# Bipolary.net
KiCad netlist of a schematic drawn in EAGLE
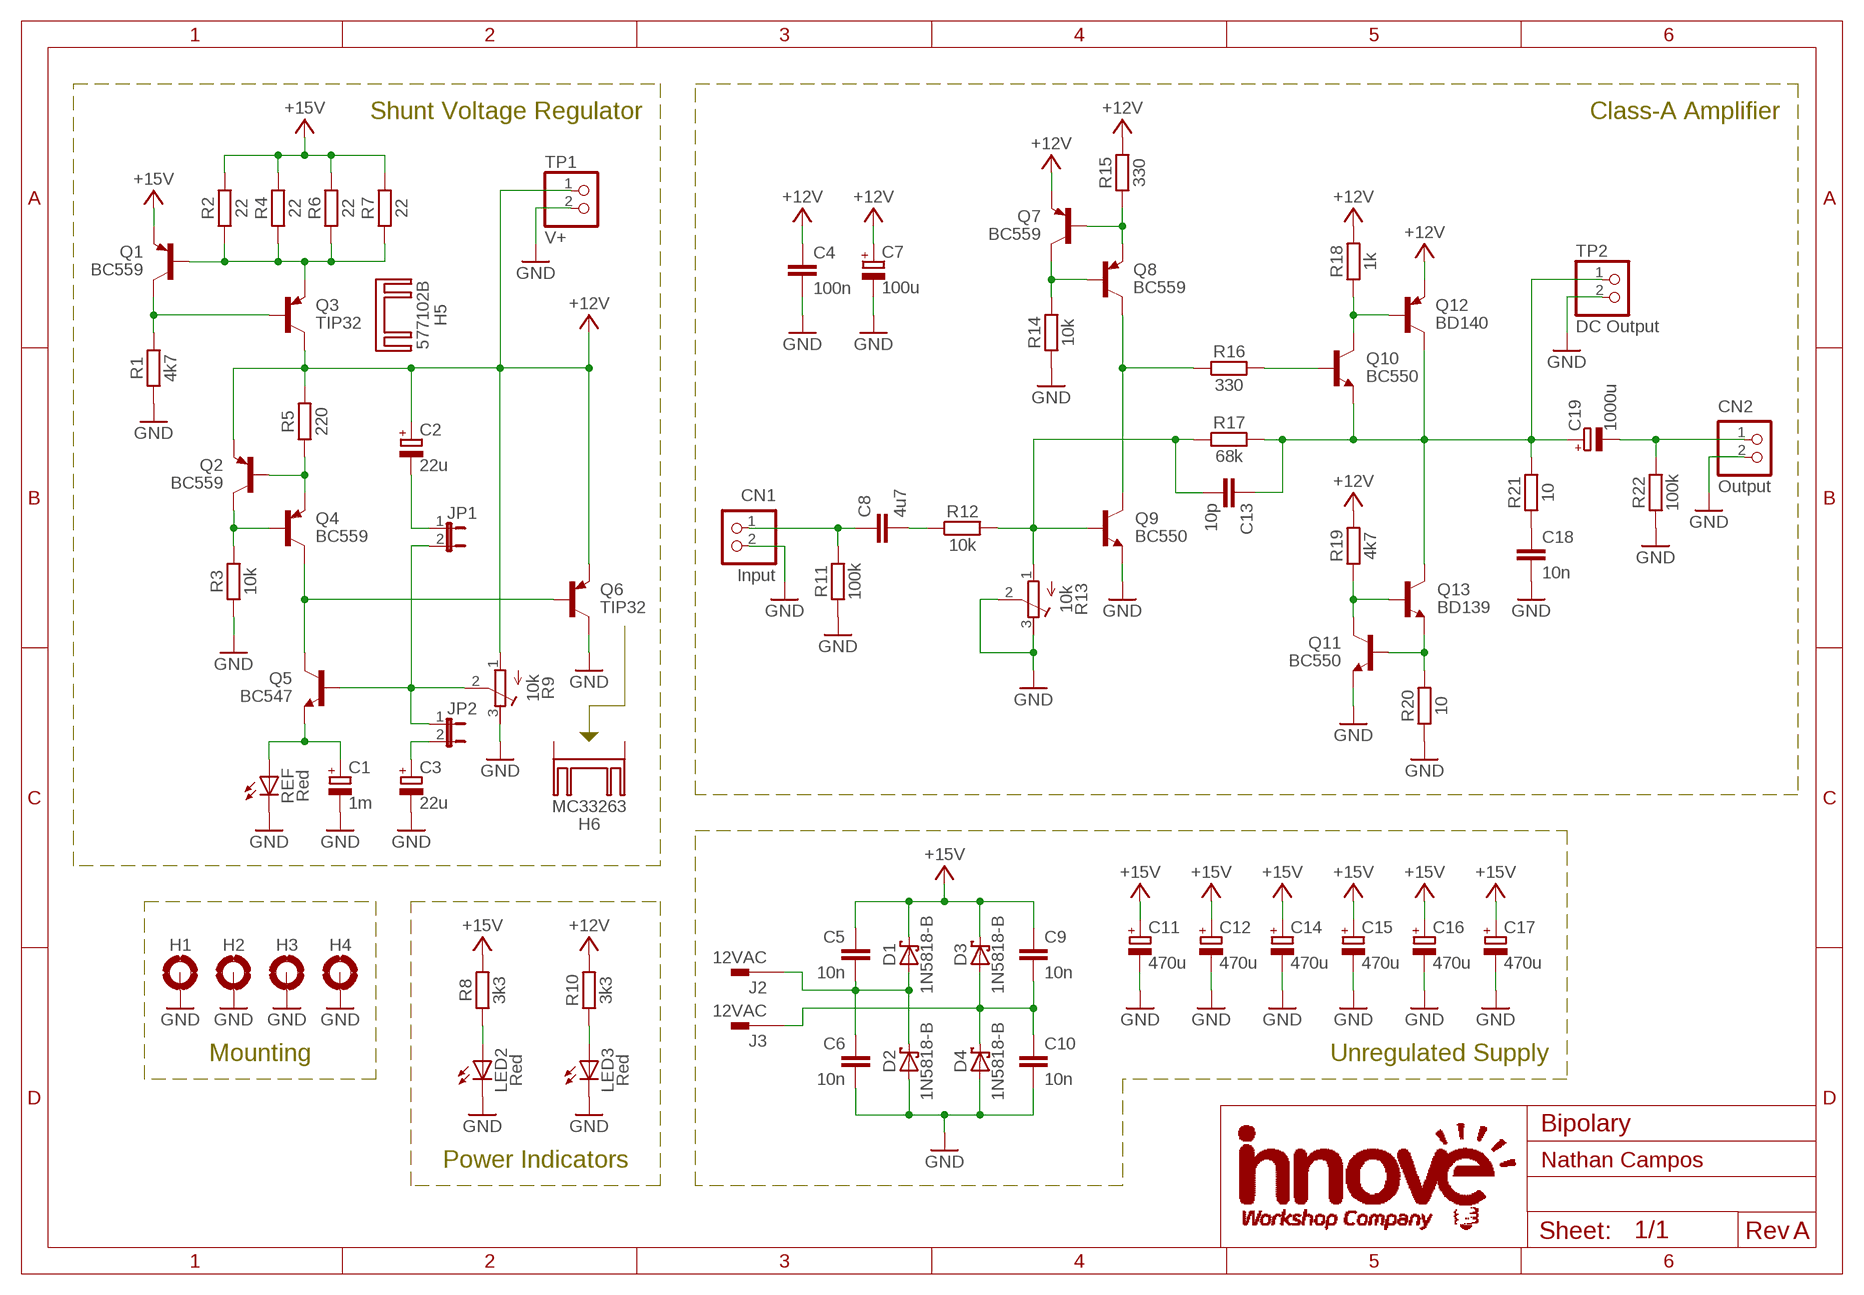
[diagram p0: schematic, sheet 1]

(export (version "E")
  (design (tool "Eeschema 10.0.6"))
  (components
    (comp (ref "C1")
      (value "1m")
      (footprint "eagle-import:E3,5-8")
      (libsource (lib "eagle-import") (part "CPOL-E3.5-8"))
    )
    (comp (ref "C2")
      (value "22u")
      (footprint "eagle-import:E2-5")
      (libsource (lib "eagle-import") (part "CPOL-E2-5"))
    )
    (comp (ref "C3")
      (value "22u")
      (footprint "eagle-import:E2-5")
      (libsource (lib "eagle-import") (part "CPOL-E2-5"))
    )
    (comp (ref "C4")
      (value "100n")
      (footprint "eagle-import:C050-025X075")
      (libsource (lib "eagle-import") (part "C5.0-2.5X7.5"))
    )
    (comp (ref "C5")
      (value "10n")
      (footprint "eagle-import:C050-025X075")
      (libsource (lib "eagle-import") (part "C5.0-2.5X7.5"))
    )
    (comp (ref "C6")
      (value "10n")
      (footprint "eagle-import:C050-025X075")
      (libsource (lib "eagle-import") (part "C5.0-2.5X7.5"))
    )
    (comp (ref "C7")
      (value "100u")
      (footprint "eagle-import:E3,5-8")
      (libsource (lib "eagle-import") (part "CPOL-E3.5-8"))
    )
    (comp (ref "C8")
      (value "4u7")
      (footprint "eagle-import:C150-084X183")
      (libsource (lib "eagle-import") (part "C15-8.4X18.3"))
    )
    (comp (ref "C9")
      (value "10n")
      (footprint "eagle-import:C050-025X075")
      (libsource (lib "eagle-import") (part "C5.0-2.5X7.5"))
    )
    (comp (ref "C10")
      (value "10n")
      (footprint "eagle-import:C050-025X075")
      (libsource (lib "eagle-import") (part "C5.0-2.5X7.5"))
    )
    (comp (ref "C11")
      (value "470u")
      (footprint "eagle-import:E5-10")
      (libsource (lib "eagle-import") (part "CPOL-E5-10"))
    )
    (comp (ref "C12")
      (value "470u")
      (footprint "eagle-import:E5-10")
      (libsource (lib "eagle-import") (part "CPOL-E5-10"))
    )
    (comp (ref "C13")
      (value "10p")
      (footprint "eagle-import:C050-025X075")
      (libsource (lib "eagle-import") (part "C5.0-2.5X7.5"))
    )
    (comp (ref "C14")
      (value "470u")
      (footprint "eagle-import:E5-10")
      (libsource (lib "eagle-import") (part "CPOL-E5-10"))
    )
    (comp (ref "C15")
      (value "470u")
      (footprint "eagle-import:E5-10")
      (libsource (lib "eagle-import") (part "CPOL-E5-10"))
    )
    (comp (ref "C16")
      (value "470u")
      (footprint "eagle-import:E5-10")
      (libsource (lib "eagle-import") (part "CPOL-E5-10"))
    )
    (comp (ref "C17")
      (value "470u")
      (footprint "eagle-import:E5-10")
      (libsource (lib "eagle-import") (part "CPOL-E5-10"))
    )
    (comp (ref "C18")
      (value "10n")
      (footprint "eagle-import:C050-025X075")
      (libsource (lib "eagle-import") (part "C5.0-2.5X7.5"))
    )
    (comp (ref "C19")
      (value "1000u")
      (footprint "eagle-import:E5-10")
      (libsource (lib "eagle-import") (part "CPOL-E5-10"))
    )
    (comp (ref "CN1")
      (value "Input")
      (footprint "eagle-import:B2B-XH-A")
      (libsource (lib "eagle-import") (part "B2B-XH-A"))
    )
    (comp (ref "CN2")
      (value "Output")
      (footprint "eagle-import:B2B-XH-A")
      (libsource (lib "eagle-import") (part "B2B-XH-A"))
    )
    (comp (ref "D1")
      (value "1N5818-B")
      (footprint "eagle-import:DO41-7.6")
      (libsource (lib "eagle-import") (part "1N5818-B"))
    )
    (comp (ref "D2")
      (value "1N5818-B")
      (footprint "eagle-import:DO41-7.6")
      (libsource (lib "eagle-import") (part "1N5818-B"))
    )
    (comp (ref "D3")
      (value "1N5818-B")
      (footprint "eagle-import:DO41-7.6")
      (libsource (lib "eagle-import") (part "1N5818-B"))
    )
    (comp (ref "D4")
      (value "1N5818-B")
      (footprint "eagle-import:DO41-7.6")
      (libsource (lib "eagle-import") (part "1N5818-B"))
    )
    (comp (ref "H1")
      (value "MOUNT-PAD-ROUND3.0")
      (footprint "eagle-import:3,0-PAD")
      (libsource (lib "eagle-import") (part "MOUNT-PAD-ROUND3.0"))
    )
    (comp (ref "H2")
      (value "MOUNT-PAD-ROUND3.0")
      (footprint "eagle-import:3,0-PAD")
      (libsource (lib "eagle-import") (part "MOUNT-PAD-ROUND3.0"))
    )
    (comp (ref "H3")
      (value "MOUNT-PAD-ROUND3.0")
      (footprint "eagle-import:3,0-PAD")
      (libsource (lib "eagle-import") (part "MOUNT-PAD-ROUND3.0"))
    )
    (comp (ref "H4")
      (value "MOUNT-PAD-ROUND3.0")
      (footprint "eagle-import:3,0-PAD")
      (libsource (lib "eagle-import") (part "MOUNT-PAD-ROUND3.0"))
    )
    (comp (ref "H5")
      (value "577102B")
      (footprint "eagle-import:D02S")
      (libsource (lib "eagle-import") (part "577102B"))
    )
    (comp (ref "H6")
      (value "MC33263")
      (footprint "eagle-import:SK104-PAD")
      (libsource (lib "eagle-import") (part "MC33263"))
    )
    (comp (ref "J2")
      (value "12VAC")
      (footprint "eagle-import:F061.100")
      (libsource (lib "eagle-import") (part "FASTON-250D140"))
    )
    (comp (ref "J3")
      (value "12VAC")
      (footprint "eagle-import:F061.100")
      (libsource (lib "eagle-import") (part "FASTON-250D140"))
    )
    (comp (ref "JP1")
      (value "JP1E")
      (footprint "eagle-import:JP1")
      (libsource (lib "eagle-import") (part "JP1E"))
    )
    (comp (ref "JP2")
      (value "JP1E")
      (footprint "eagle-import:JP1")
      (libsource (lib "eagle-import") (part "JP1E"))
    )
    (comp (ref "LED2")
      (value "Red")
      (footprint "eagle-import:LED5MM")
      (libsource (lib "eagle-import") (part "LED5MM"))
    )
    (comp (ref "LED3")
      (value "Red")
      (footprint "eagle-import:LED5MM")
      (libsource (lib "eagle-import") (part "LED5MM"))
    )
    (comp (ref "Q1")
      (value "BC559")
      (footprint "eagle-import:TO92")
      (libsource (lib "eagle-import") (part "BC559"))
    )
    (comp (ref "Q2")
      (value "BC559")
      (footprint "eagle-import:TO92")
      (libsource (lib "eagle-import") (part "BC559"))
    )
    (comp (ref "Q3")
      (value "TIP32")
      (footprint "eagle-import:TO220V")
      (libsource (lib "eagle-import") (part "TIP32"))
    )
    (comp (ref "Q4")
      (value "BC559")
      (footprint "eagle-import:TO92")
      (libsource (lib "eagle-import") (part "BC559"))
    )
    (comp (ref "Q5")
      (value "BC547")
      (footprint "eagle-import:TO92")
      (libsource (lib "eagle-import") (part "BC547"))
    )
    (comp (ref "Q6")
      (value "TIP32")
      (footprint "eagle-import:TO220V")
      (libsource (lib "eagle-import") (part "TIP32"))
    )
    (comp (ref "Q7")
      (value "BC559")
      (footprint "eagle-import:TO92")
      (libsource (lib "eagle-import") (part "BC559"))
    )
    (comp (ref "Q8")
      (value "BC559")
      (footprint "eagle-import:TO92")
      (libsource (lib "eagle-import") (part "BC559"))
    )
    (comp (ref "Q9")
      (value "BC550")
      (footprint "eagle-import:TO92")
      (libsource (lib "eagle-import") (part "BC550"))
    )
    (comp (ref "Q10")
      (value "BC550")
      (footprint "eagle-import:TO92")
      (libsource (lib "eagle-import") (part "BC550"))
    )
    (comp (ref "Q11")
      (value "BC550")
      (footprint "eagle-import:TO92")
      (libsource (lib "eagle-import") (part "BC550"))
    )
    (comp (ref "Q12")
      (value "BD140")
      (footprint "eagle-import:TO126V")
      (libsource (lib "eagle-import") (part "BD140"))
    )
    (comp (ref "Q13")
      (value "BD139")
      (footprint "eagle-import:TO126V")
      (libsource (lib "eagle-import") (part "BD139"))
    )
    (comp (ref "R1")
      (value "4k7")
      (footprint "eagle-import:0207_10")
      (libsource (lib "eagle-import") (part "RT0207"))
    )
    (comp (ref "R2")
      (value "22")
      (footprint "eagle-import:0207_10")
      (libsource (lib "eagle-import") (part "RT0207"))
    )
    (comp (ref "R3")
      (value "10k")
      (footprint "eagle-import:0207_10")
      (libsource (lib "eagle-import") (part "RT0207"))
    )
    (comp (ref "R4")
      (value "22")
      (footprint "eagle-import:0207_10")
      (libsource (lib "eagle-import") (part "RT0207"))
    )
    (comp (ref "R5")
      (value "220")
      (footprint "eagle-import:0207_10")
      (libsource (lib "eagle-import") (part "RT0207"))
    )
    (comp (ref "R6")
      (value "22")
      (footprint "eagle-import:0207_10")
      (libsource (lib "eagle-import") (part "RT0207"))
    )
    (comp (ref "R7")
      (value "22")
      (footprint "eagle-import:0207_10")
      (libsource (lib "eagle-import") (part "RT0207"))
    )
    (comp (ref "R8")
      (value "3k3")
      (footprint "eagle-import:0207_10")
      (libsource (lib "eagle-import") (part "RT0207"))
    )
    (comp (ref "R9")
      (value "10k")
      (footprint "eagle-import:RTRIM3296Y")
      (libsource (lib "eagle-import") (part "R-TRIMM3296Y"))
    )
    (comp (ref "R10")
      (value "3k3")
      (footprint "eagle-import:0207_10")
      (libsource (lib "eagle-import") (part "RT0207"))
    )
    (comp (ref "R11")
      (value "100k")
      (footprint "eagle-import:0207_10")
      (libsource (lib "eagle-import") (part "RT0207"))
    )
    (comp (ref "R12")
      (value "10k")
      (footprint "eagle-import:0207_10")
      (libsource (lib "eagle-import") (part "RT0207"))
    )
    (comp (ref "R13")
      (value "10k")
      (footprint "eagle-import:RTRIM3296Y")
      (libsource (lib "eagle-import") (part "R-TRIMM3296Y"))
    )
    (comp (ref "R14")
      (value "10k")
      (footprint "eagle-import:0207_10")
      (libsource (lib "eagle-import") (part "RT0207"))
    )
    (comp (ref "R15")
      (value "330")
      (footprint "eagle-import:0207_10")
      (libsource (lib "eagle-import") (part "RT0207"))
    )
    (comp (ref "R16")
      (value "330")
      (footprint "eagle-import:0207_10")
      (libsource (lib "eagle-import") (part "RT0207"))
    )
    (comp (ref "R17")
      (value "68k")
      (footprint "eagle-import:0207_10")
      (libsource (lib "eagle-import") (part "RT0207"))
    )
    (comp (ref "R18")
      (value "1k")
      (footprint "eagle-import:0207_10")
      (libsource (lib "eagle-import") (part "RT0207"))
    )
    (comp (ref "R19")
      (value "4k7")
      (footprint "eagle-import:0207_10")
      (libsource (lib "eagle-import") (part "RT0207"))
    )
    (comp (ref "R20")
      (value "10")
      (footprint "eagle-import:0207_10")
      (libsource (lib "eagle-import") (part "RT0207"))
    )
    (comp (ref "R21")
      (value "10")
      (footprint "eagle-import:0207_10")
      (libsource (lib "eagle-import") (part "RT0207"))
    )
    (comp (ref "R22")
      (value "100k")
      (footprint "eagle-import:0207_10")
      (libsource (lib "eagle-import") (part "RT0207"))
    )
    (comp (ref "REF")
      (value "Red")
      (footprint "eagle-import:LED5MM")
      (libsource (lib "eagle-import") (part "LED5MM"))
    )
    (comp (ref "TP1")
      (value "V+")
      (footprint "eagle-import:1X02")
      (libsource (lib "eagle-import") (part "PINHD-1X2"))
    )
    (comp (ref "TP2")
      (value "DC Output")
      (footprint "eagle-import:1X02")
      (libsource (lib "eagle-import") (part "PINHD-1X2"))
    )
  )
  (nets
    (net (code "1") (name "+12V") (class "Default")
      (node (ref "C2") (pin "+") (pinfunction "+_+") (pintype "passive"))
      (node (ref "C4") (pin "1") (pinfunction "1_1") (pintype "passive"))
      (node (ref "C7") (pin "+") (pinfunction "+_+") (pintype "passive"))
      (node (ref "Q12") (pin "1") (pinfunction "E_1") (pintype "passive"))
      (node (ref "Q2") (pin "3") (pinfunction "E_3") (pintype "passive"))
      (node (ref "Q3") (pin "2") (pinfunction "C_2") (pintype "passive"))
      (node (ref "Q6") (pin "3") (pinfunction "E_3") (pintype "passive"))
      (node (ref "Q7") (pin "3") (pinfunction "E_3") (pintype "passive"))
      (node (ref "R10") (pin "2") (pinfunction "2_2") (pintype "passive"))
      (node (ref "R15") (pin "2") (pinfunction "2_2") (pintype "passive"))
      (node (ref "R18") (pin "2") (pinfunction "2_2") (pintype "passive"))
      (node (ref "R19") (pin "2") (pinfunction "2_2") (pintype "passive"))
      (node (ref "R5") (pin "2") (pinfunction "2_2") (pintype "passive"))
      (node (ref "R9") (pin "1") (pinfunction "A_1") (pintype "passive"))
      (node (ref "TP1") (pin "1") (pinfunction "1_1") (pintype "passive"))
    )
    (net (code "2") (name "+15V") (class "Default")
      (node (ref "C11") (pin "+") (pinfunction "+_+") (pintype "passive"))
      (node (ref "C12") (pin "+") (pinfunction "+_+") (pintype "passive"))
      (node (ref "C14") (pin "+") (pinfunction "+_+") (pintype "passive"))
      (node (ref "C15") (pin "+") (pinfunction "+_+") (pintype "passive"))
      (node (ref "C16") (pin "+") (pinfunction "+_+") (pintype "passive"))
      (node (ref "C17") (pin "+") (pinfunction "+_+") (pintype "passive"))
      (node (ref "C5") (pin "1") (pinfunction "1_1") (pintype "passive"))
      (node (ref "C9") (pin "1") (pinfunction "1_1") (pintype "passive"))
      (node (ref "D1") (pin "C") (pinfunction "C_C") (pintype "passive"))
      (node (ref "D3") (pin "C") (pinfunction "C_C") (pintype "passive"))
      (node (ref "Q1") (pin "3") (pinfunction "E_3") (pintype "passive"))
      (node (ref "R2") (pin "2") (pinfunction "2_2") (pintype "passive"))
      (node (ref "R4") (pin "2") (pinfunction "2_2") (pintype "passive"))
      (node (ref "R6") (pin "2") (pinfunction "2_2") (pintype "passive"))
      (node (ref "R7") (pin "2") (pinfunction "2_2") (pintype "passive"))
      (node (ref "R8") (pin "2") (pinfunction "2_2") (pintype "passive"))
    )
    (net (code "3") (name "GND") (class "Default")
      (node (ref "C1") (pin "-") (pinfunction "-_-") (pintype "passive"))
      (node (ref "C10") (pin "2") (pinfunction "2_2") (pintype "passive"))
      (node (ref "C11") (pin "-") (pinfunction "-_-") (pintype "passive"))
      (node (ref "C12") (pin "-") (pinfunction "-_-") (pintype "passive"))
      (node (ref "C14") (pin "-") (pinfunction "-_-") (pintype "passive"))
      (node (ref "C15") (pin "-") (pinfunction "-_-") (pintype "passive"))
      (node (ref "C16") (pin "-") (pinfunction "-_-") (pintype "passive"))
      (node (ref "C17") (pin "-") (pinfunction "-_-") (pintype "passive"))
      (node (ref "C18") (pin "2") (pinfunction "2_2") (pintype "passive"))
      (node (ref "C3") (pin "-") (pinfunction "-_-") (pintype "passive"))
      (node (ref "C4") (pin "2") (pinfunction "2_2") (pintype "passive"))
      (node (ref "C6") (pin "2") (pinfunction "2_2") (pintype "passive"))
      (node (ref "C7") (pin "-") (pinfunction "-_-") (pintype "passive"))
      (node (ref "CN1") (pin "2") (pinfunction "2_2") (pintype "passive"))
      (node (ref "CN2") (pin "2") (pinfunction "2_2") (pintype "passive"))
      (node (ref "D2") (pin "A") (pinfunction "A_A") (pintype "passive"))
      (node (ref "D4") (pin "A") (pinfunction "A_A") (pintype "passive"))
      (node (ref "H1") (pin "B3,0") (pinfunction "MOUNT_B3,0") (pintype "passive"))
      (node (ref "H2") (pin "B3,0") (pinfunction "MOUNT_B3,0") (pintype "passive"))
      (node (ref "H3") (pin "B3,0") (pinfunction "MOUNT_B3,0") (pintype "passive"))
      (node (ref "H4") (pin "B3,0") (pinfunction "MOUNT_B3,0") (pintype "passive"))
      (node (ref "LED2") (pin "K") (pinfunction "C_K") (pintype "passive"))
      (node (ref "LED3") (pin "K") (pinfunction "C_K") (pintype "passive"))
      (node (ref "Q11") (pin "3") (pinfunction "E_3") (pintype "passive"))
      (node (ref "Q6") (pin "2") (pinfunction "C_2") (pintype "passive"))
      (node (ref "Q9") (pin "3") (pinfunction "E_3") (pintype "passive"))
      (node (ref "R1") (pin "1") (pinfunction "1_1") (pintype "passive"))
      (node (ref "R11") (pin "1") (pinfunction "1_1") (pintype "passive"))
      (node (ref "R13") (pin "2") (pinfunction "S_2") (pintype "passive"))
      (node (ref "R13") (pin "3") (pinfunction "E_3") (pintype "passive"))
      (node (ref "R14") (pin "1") (pinfunction "1_1") (pintype "passive"))
      (node (ref "R20") (pin "1") (pinfunction "1_1") (pintype "passive"))
      (node (ref "R22") (pin "1") (pinfunction "1_1") (pintype "passive"))
      (node (ref "R3") (pin "1") (pinfunction "1_1") (pintype "passive"))
      (node (ref "R9") (pin "3") (pinfunction "E_3") (pintype "passive"))
      (node (ref "REF") (pin "K") (pinfunction "C_K") (pintype "passive"))
      (node (ref "TP1") (pin "2") (pinfunction "2_2") (pintype "passive"))
      (node (ref "TP2") (pin "2") (pinfunction "2_2") (pintype "passive"))
    )
    (net (code "4") (name "Net-(C2-Pad-)") (class "Default")
      (node (ref "C2") (pin "-") (pinfunction "-_-") (pintype "passive"))
      (node (ref "JP1") (pin "1") (pinfunction "1_1") (pintype "passive"))
    )
    (net (code "5") (name "Net-(C3-Pad+)") (class "Default")
      (node (ref "C3") (pin "+") (pinfunction "+_+") (pintype "passive"))
      (node (ref "JP2") (pin "2") (pinfunction "2_2") (pintype "passive"))
    )
    (net (code "6") (name "Net-(C5-Pad2)") (class "Default")
      (node (ref "C5") (pin "2") (pinfunction "2_2") (pintype "passive"))
      (node (ref "C6") (pin "1") (pinfunction "1_1") (pintype "passive"))
      (node (ref "D1") (pin "A") (pinfunction "A_A") (pintype "passive"))
      (node (ref "D2") (pin "C") (pinfunction "C_C") (pintype "passive"))
      (node (ref "J2") (pin "A1") (pinfunction "1_A1") (pintype "passive"))
      (node (ref "J2") (pin "A2") (pinfunction "1_A2") (pintype "passive"))
    )
    (net (code "7") (name "Net-(C8-Pad1)") (class "Default")
      (node (ref "C8") (pin "1") (pinfunction "1_1") (pintype "passive"))
      (node (ref "CN1") (pin "1") (pinfunction "1_1") (pintype "passive"))
      (node (ref "R11") (pin "2") (pinfunction "2_2") (pintype "passive"))
    )
    (net (code "8") (name "Net-(C8-Pad2)") (class "Default")
      (node (ref "C8") (pin "2") (pinfunction "2_2") (pintype "passive"))
      (node (ref "R12") (pin "1") (pinfunction "1_1") (pintype "passive"))
    )
    (net (code "9") (name "Net-(C10-Pad1)") (class "Default")
      (node (ref "C10") (pin "1") (pinfunction "1_1") (pintype "passive"))
      (node (ref "C9") (pin "2") (pinfunction "2_2") (pintype "passive"))
      (node (ref "D3") (pin "A") (pinfunction "A_A") (pintype "passive"))
      (node (ref "D4") (pin "C") (pinfunction "C_C") (pintype "passive"))
      (node (ref "J3") (pin "A1") (pinfunction "1_A1") (pintype "passive"))
      (node (ref "J3") (pin "A2") (pinfunction "1_A2") (pintype "passive"))
    )
    (net (code "10") (name "Net-(C18-Pad1)") (class "Default")
      (node (ref "C18") (pin "1") (pinfunction "1_1") (pintype "passive"))
      (node (ref "R21") (pin "1") (pinfunction "1_1") (pintype "passive"))
    )
    (net (code "11") (name "Net-(C19-Pad-)") (class "Default")
      (node (ref "C19") (pin "-") (pinfunction "-_-") (pintype "passive"))
      (node (ref "CN2") (pin "1") (pinfunction "1_1") (pintype "passive"))
      (node (ref "R22") (pin "2") (pinfunction "2_2") (pintype "passive"))
    )
    (net (code "12") (name "Net-(LED2-PadA)") (class "Default")
      (node (ref "LED2") (pin "A") (pinfunction "A_A") (pintype "passive"))
      (node (ref "R8") (pin "1") (pinfunction "1_1") (pintype "passive"))
    )
    (net (code "13") (name "Net-(LED3-PadA)") (class "Default")
      (node (ref "LED3") (pin "A") (pinfunction "A_A") (pintype "passive"))
      (node (ref "R10") (pin "1") (pinfunction "1_1") (pintype "passive"))
    )
    (net (code "14") (name "Net-(Q1-B)") (class "Default")
      (node (ref "Q1") (pin "2") (pinfunction "B_2") (pintype "passive"))
      (node (ref "Q3") (pin "3") (pinfunction "E_3") (pintype "passive"))
      (node (ref "R2") (pin "1") (pinfunction "1_1") (pintype "passive"))
      (node (ref "R4") (pin "1") (pinfunction "1_1") (pintype "passive"))
      (node (ref "R6") (pin "1") (pinfunction "1_1") (pintype "passive"))
      (node (ref "R7") (pin "1") (pinfunction "1_1") (pintype "passive"))
    )
    (net (code "15") (name "Net-(Q1-C)") (class "Default")
      (node (ref "Q1") (pin "1") (pinfunction "C_1") (pintype "passive"))
      (node (ref "Q3") (pin "1") (pinfunction "B_1") (pintype "passive"))
      (node (ref "R1") (pin "2") (pinfunction "2_2") (pintype "passive"))
    )
    (net (code "16") (name "Net-(Q2-B)") (class "Default")
      (node (ref "Q2") (pin "2") (pinfunction "B_2") (pintype "passive"))
      (node (ref "Q4") (pin "3") (pinfunction "E_3") (pintype "passive"))
      (node (ref "R5") (pin "1") (pinfunction "1_1") (pintype "passive"))
    )
    (net (code "17") (name "Net-(Q2-C)") (class "Default")
      (node (ref "Q2") (pin "1") (pinfunction "C_1") (pintype "passive"))
      (node (ref "Q4") (pin "2") (pinfunction "B_2") (pintype "passive"))
      (node (ref "R3") (pin "2") (pinfunction "2_2") (pintype "passive"))
    )
    (net (code "18") (name "Net-(Q4-C)") (class "Default")
      (node (ref "Q4") (pin "1") (pinfunction "C_1") (pintype "passive"))
      (node (ref "Q5") (pin "1") (pinfunction "C_1") (pintype "passive"))
      (node (ref "Q6") (pin "1") (pinfunction "B_1") (pintype "passive"))
    )
    (net (code "19") (name "Net-(Q5-B)") (class "Default")
      (node (ref "JP1") (pin "2") (pinfunction "2_2") (pintype "passive"))
      (node (ref "JP2") (pin "1") (pinfunction "1_1") (pintype "passive"))
      (node (ref "Q5") (pin "2") (pinfunction "B_2") (pintype "passive"))
      (node (ref "R9") (pin "2") (pinfunction "S_2") (pintype "passive"))
    )
    (net (code "20") (name "Net-(Q5-E)") (class "Default")
      (node (ref "C1") (pin "+") (pinfunction "+_+") (pintype "passive"))
      (node (ref "Q5") (pin "3") (pinfunction "E_3") (pintype "passive"))
      (node (ref "REF") (pin "A") (pinfunction "A_A") (pintype "passive"))
    )
    (net (code "21") (name "Net-(Q7-B)") (class "Default")
      (node (ref "Q7") (pin "2") (pinfunction "B_2") (pintype "passive"))
      (node (ref "Q8") (pin "3") (pinfunction "E_3") (pintype "passive"))
      (node (ref "R15") (pin "1") (pinfunction "1_1") (pintype "passive"))
    )
    (net (code "22") (name "Net-(Q7-C)") (class "Default")
      (node (ref "Q7") (pin "1") (pinfunction "C_1") (pintype "passive"))
      (node (ref "Q8") (pin "2") (pinfunction "B_2") (pintype "passive"))
      (node (ref "R14") (pin "2") (pinfunction "2_2") (pintype "passive"))
    )
    (net (code "23") (name "Net-(Q8-C)") (class "Default")
      (node (ref "Q8") (pin "1") (pinfunction "C_1") (pintype "passive"))
      (node (ref "Q9") (pin "1") (pinfunction "C_1") (pintype "passive"))
      (node (ref "R16") (pin "1") (pinfunction "1_1") (pintype "passive"))
    )
    (net (code "24") (name "Net-(Q9-B)") (class "Default")
      (node (ref "C13") (pin "2") (pinfunction "2_2") (pintype "passive"))
      (node (ref "Q9") (pin "2") (pinfunction "B_2") (pintype "passive"))
      (node (ref "R12") (pin "2") (pinfunction "2_2") (pintype "passive"))
      (node (ref "R13") (pin "1") (pinfunction "A_1") (pintype "passive"))
      (node (ref "R17") (pin "1") (pinfunction "1_1") (pintype "passive"))
    )
    (net (code "25") (name "Net-(Q10-B)") (class "Default")
      (node (ref "Q10") (pin "2") (pinfunction "B_2") (pintype "passive"))
      (node (ref "R16") (pin "2") (pinfunction "2_2") (pintype "passive"))
    )
    (net (code "26") (name "Net-(Q10-C)") (class "Default")
      (node (ref "Q10") (pin "1") (pinfunction "C_1") (pintype "passive"))
      (node (ref "Q12") (pin "3") (pinfunction "B_3") (pintype "passive"))
      (node (ref "R18") (pin "1") (pinfunction "1_1") (pintype "passive"))
    )
    (net (code "27") (name "Net-(Q10-E)") (class "Default")
      (node (ref "C13") (pin "1") (pinfunction "1_1") (pintype "passive"))
      (node (ref "C19") (pin "+") (pinfunction "+_+") (pintype "passive"))
      (node (ref "Q10") (pin "3") (pinfunction "E_3") (pintype "passive"))
      (node (ref "Q12") (pin "2") (pinfunction "C_2") (pintype "passive"))
      (node (ref "Q13") (pin "2") (pinfunction "C_2") (pintype "passive"))
      (node (ref "R17") (pin "2") (pinfunction "2_2") (pintype "passive"))
      (node (ref "R21") (pin "2") (pinfunction "2_2") (pintype "passive"))
      (node (ref "TP2") (pin "1") (pinfunction "1_1") (pintype "passive"))
    )
    (net (code "28") (name "Net-(Q11-B)") (class "Default")
      (node (ref "Q11") (pin "2") (pinfunction "B_2") (pintype "passive"))
      (node (ref "Q13") (pin "1") (pinfunction "E_1") (pintype "passive"))
      (node (ref "R20") (pin "2") (pinfunction "2_2") (pintype "passive"))
    )
    (net (code "29") (name "Net-(Q11-C)") (class "Default")
      (node (ref "Q11") (pin "1") (pinfunction "C_1") (pintype "passive"))
      (node (ref "Q13") (pin "3") (pinfunction "B_3") (pintype "passive"))
      (node (ref "R19") (pin "1") (pinfunction "1_1") (pintype "passive"))
    )
    (net (code "30") (name "unconnected-(H6-K-PadK1)") (class "Default")
      (node (ref "H6") (pin "K1") (pinfunction "K_K1") (pintype "passive"))
    )
    (net (code "31") (name "unconnected-(H6-K-PadK2)") (class "Default")
      (node (ref "H6") (pin "K2") (pinfunction "K_K2") (pintype "passive"))
    )
  )
)
